# eib-64-nanoz-adapter.net
KiCad netlist of a schematic drawn in EAGLE
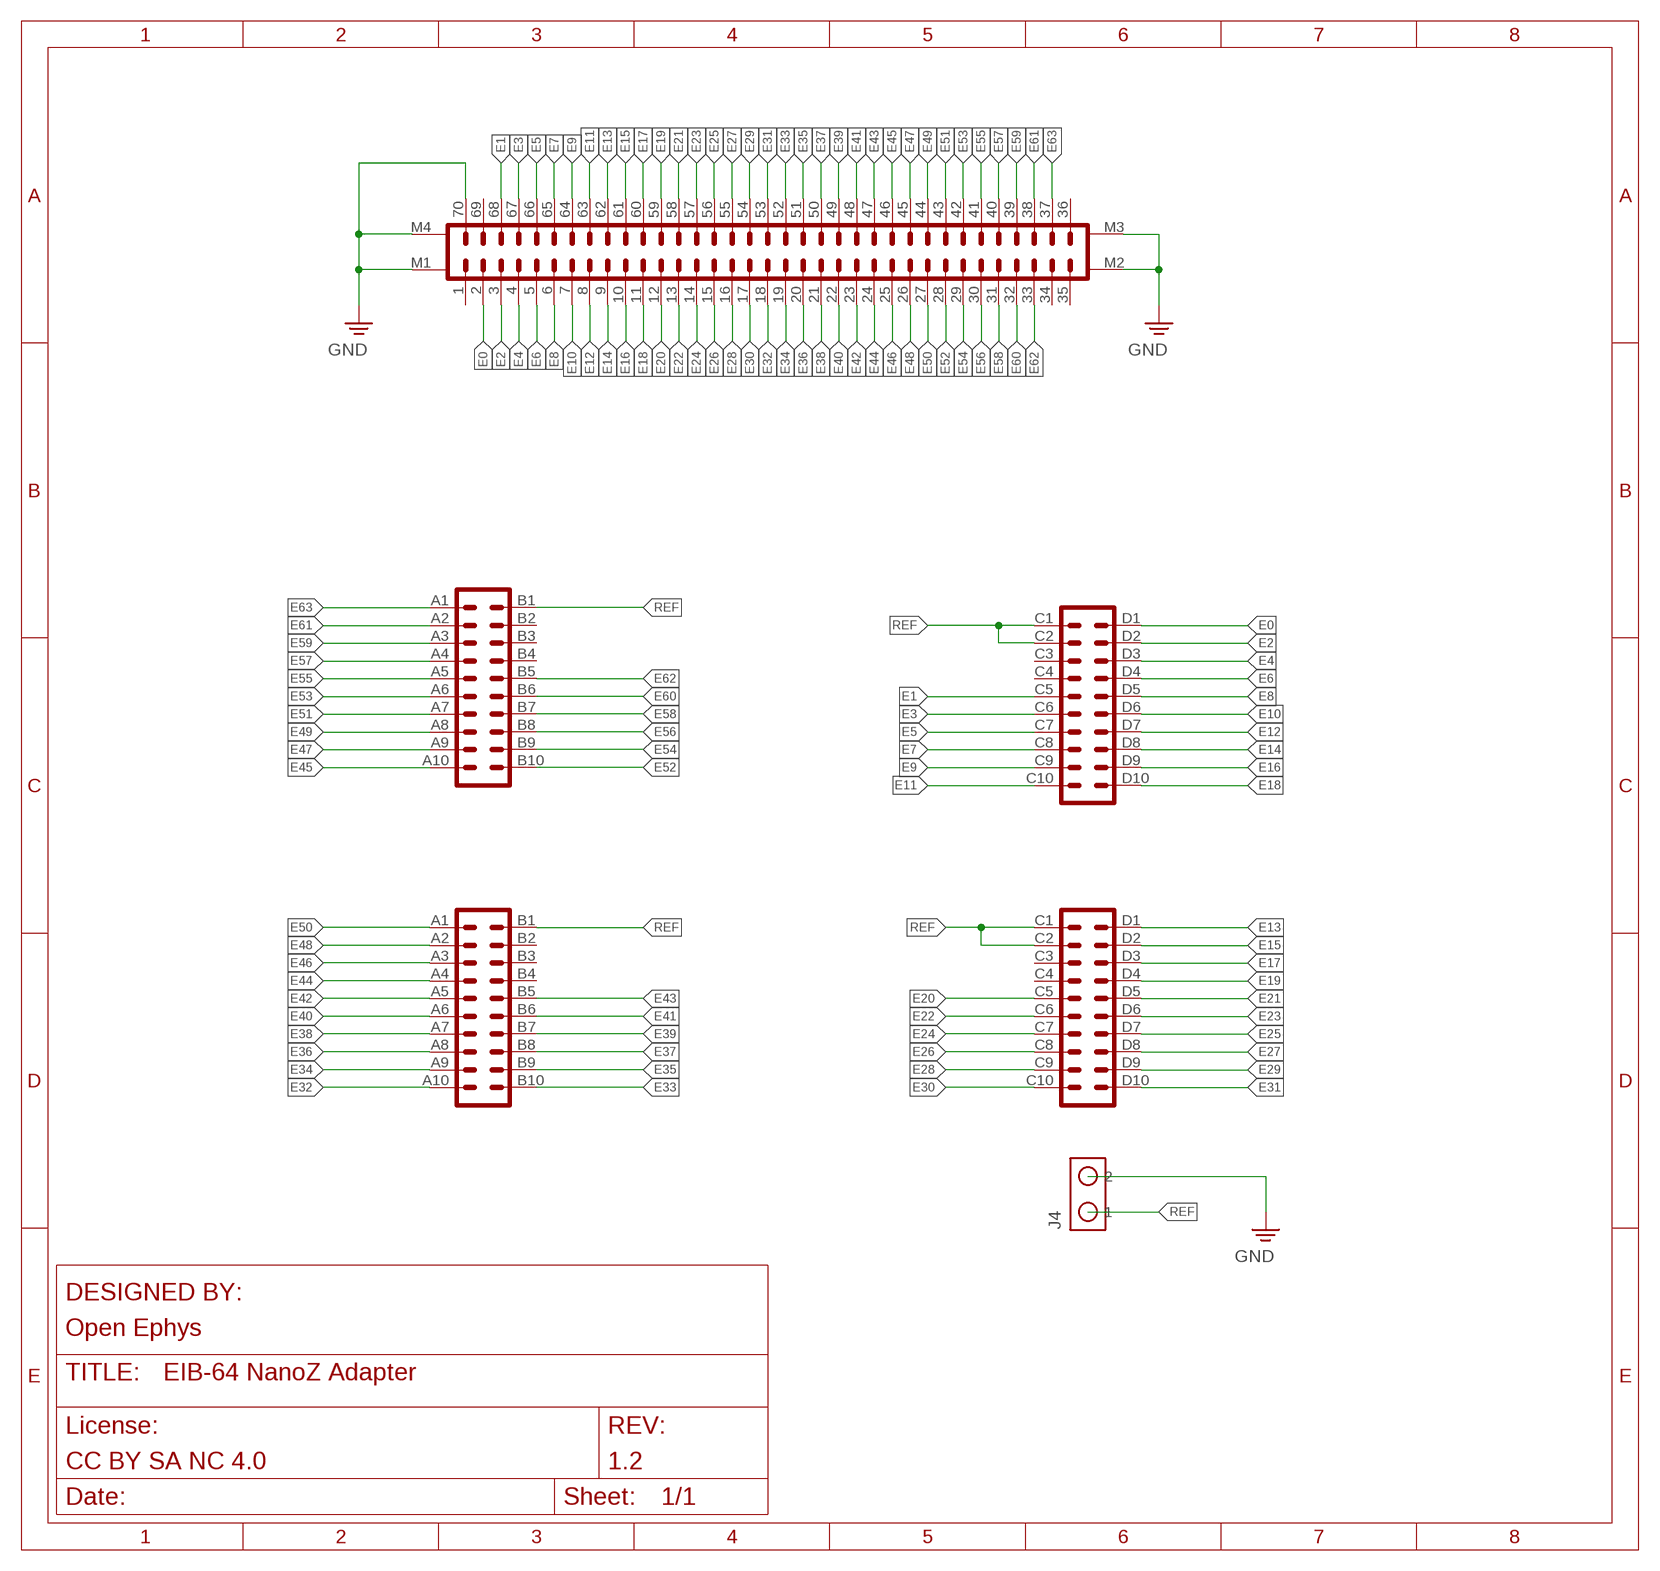
[diagram p0: schematic, sheet 1]

(export (version "E")
  (design (tool "Eeschema 10.0.6"))
  (components
    (comp (ref "J1")
      (value "DF40-REC")
      (footprint "eagle-import:DF40-70HEAD")
      (libsource (lib "eagle-import") (part "PINHD-2X35+4_DF40-70HEAD"))
    )
    (comp (ref "J2")
      (value "PINHD-4X10_MOLC-THRU")
      (footprint "eagle-import:MOLC-110-11-S-Q")
      (libsource (lib "eagle-import") (part "PINHD-4X10_MOLC-THRU"))
    )
    (comp (ref "J3")
      (value "PINHD-4X10_MOLC-THRU")
      (footprint "eagle-import:MOLC-110-11-S-Q")
      (libsource (lib "eagle-import") (part "PINHD-4X10_MOLC-THRU"))
    )
    (comp (ref "J4")
      (value "SCREW2")
      (footprint "eagle-import:SCREW2")
      (libsource (lib "eagle-import") (part "SCREW2"))
    )
  )
  (nets
    (net (code "1") (name "E0") (class "Default")
      (node (ref "J1") (pin "2") (pinfunction "2_2") (pintype "bidirectional"))
      (node (ref "J2") (pin "D1") (pinfunction "20_D1") (pintype "bidirectional"))
    )
    (net (code "2") (name "E1") (class "Default")
      (node (ref "J1") (pin "68") (pinfunction "68_68") (pintype "bidirectional"))
      (node (ref "J2") (pin "C5") (pinfunction "5_C5") (pintype "bidirectional"))
    )
    (net (code "3") (name "E2") (class "Default")
      (node (ref "J1") (pin "3") (pinfunction "3_3") (pintype "bidirectional"))
      (node (ref "J2") (pin "D2") (pinfunction "19_D2") (pintype "bidirectional"))
    )
    (net (code "4") (name "E3") (class "Default")
      (node (ref "J1") (pin "67") (pinfunction "67_67") (pintype "bidirectional"))
      (node (ref "J2") (pin "C6") (pinfunction "6_C6") (pintype "bidirectional"))
    )
    (net (code "5") (name "E4") (class "Default")
      (node (ref "J1") (pin "4") (pinfunction "4_4") (pintype "bidirectional"))
      (node (ref "J2") (pin "D3") (pinfunction "18_D3") (pintype "bidirectional"))
    )
    (net (code "6") (name "E5") (class "Default")
      (node (ref "J1") (pin "66") (pinfunction "66_66") (pintype "bidirectional"))
      (node (ref "J2") (pin "C7") (pinfunction "7_C7") (pintype "bidirectional"))
    )
    (net (code "7") (name "E6") (class "Default")
      (node (ref "J1") (pin "5") (pinfunction "5_5") (pintype "bidirectional"))
      (node (ref "J2") (pin "D4") (pinfunction "17_D4") (pintype "bidirectional"))
    )
    (net (code "8") (name "E7") (class "Default")
      (node (ref "J1") (pin "65") (pinfunction "65_65") (pintype "bidirectional"))
      (node (ref "J2") (pin "C8") (pinfunction "8_C8") (pintype "bidirectional"))
    )
    (net (code "9") (name "E8") (class "Default")
      (node (ref "J1") (pin "6") (pinfunction "6_6") (pintype "bidirectional"))
      (node (ref "J2") (pin "D5") (pinfunction "16_D5") (pintype "bidirectional"))
    )
    (net (code "10") (name "E9") (class "Default")
      (node (ref "J1") (pin "64") (pinfunction "64_64") (pintype "bidirectional"))
      (node (ref "J2") (pin "C9") (pinfunction "9_C9") (pintype "bidirectional"))
    )
    (net (code "11") (name "E10") (class "Default")
      (node (ref "J1") (pin "7") (pinfunction "7_7") (pintype "bidirectional"))
      (node (ref "J2") (pin "D6") (pinfunction "15_D6") (pintype "bidirectional"))
    )
    (net (code "12") (name "E11") (class "Default")
      (node (ref "J1") (pin "63") (pinfunction "63_63") (pintype "bidirectional"))
      (node (ref "J2") (pin "C10") (pinfunction "10_C10") (pintype "bidirectional"))
    )
    (net (code "13") (name "E12") (class "Default")
      (node (ref "J1") (pin "8") (pinfunction "8_8") (pintype "bidirectional"))
      (node (ref "J2") (pin "D7") (pinfunction "14_D7") (pintype "bidirectional"))
    )
    (net (code "14") (name "E13") (class "Default")
      (node (ref "J1") (pin "62") (pinfunction "62_62") (pintype "bidirectional"))
      (node (ref "J3") (pin "D1") (pinfunction "20_D1") (pintype "bidirectional"))
    )
    (net (code "15") (name "E14") (class "Default")
      (node (ref "J1") (pin "9") (pinfunction "9_9") (pintype "bidirectional"))
      (node (ref "J2") (pin "D8") (pinfunction "13_D8") (pintype "bidirectional"))
    )
    (net (code "16") (name "E15") (class "Default")
      (node (ref "J1") (pin "61") (pinfunction "61_61") (pintype "bidirectional"))
      (node (ref "J3") (pin "D2") (pinfunction "19_D2") (pintype "bidirectional"))
    )
    (net (code "17") (name "E16") (class "Default")
      (node (ref "J1") (pin "10") (pinfunction "10_10") (pintype "bidirectional"))
      (node (ref "J2") (pin "D9") (pinfunction "12_D9") (pintype "bidirectional"))
    )
    (net (code "18") (name "E17") (class "Default")
      (node (ref "J1") (pin "60") (pinfunction "60_60") (pintype "bidirectional"))
      (node (ref "J3") (pin "D3") (pinfunction "18_D3") (pintype "bidirectional"))
    )
    (net (code "19") (name "E18") (class "Default")
      (node (ref "J1") (pin "11") (pinfunction "11_11") (pintype "bidirectional"))
      (node (ref "J2") (pin "D10") (pinfunction "11_D10") (pintype "bidirectional"))
    )
    (net (code "20") (name "E19") (class "Default")
      (node (ref "J1") (pin "59") (pinfunction "59_59") (pintype "bidirectional"))
      (node (ref "J3") (pin "D4") (pinfunction "17_D4") (pintype "bidirectional"))
    )
    (net (code "21") (name "E20") (class "Default")
      (node (ref "J1") (pin "12") (pinfunction "12_12") (pintype "bidirectional"))
      (node (ref "J3") (pin "C5") (pinfunction "5_C5") (pintype "bidirectional"))
    )
    (net (code "22") (name "E21") (class "Default")
      (node (ref "J1") (pin "58") (pinfunction "58_58") (pintype "bidirectional"))
      (node (ref "J3") (pin "D5") (pinfunction "16_D5") (pintype "bidirectional"))
    )
    (net (code "23") (name "E22") (class "Default")
      (node (ref "J1") (pin "13") (pinfunction "13_13") (pintype "bidirectional"))
      (node (ref "J3") (pin "C6") (pinfunction "6_C6") (pintype "bidirectional"))
    )
    (net (code "24") (name "E23") (class "Default")
      (node (ref "J1") (pin "57") (pinfunction "57_57") (pintype "bidirectional"))
      (node (ref "J3") (pin "D6") (pinfunction "15_D6") (pintype "bidirectional"))
    )
    (net (code "25") (name "E24") (class "Default")
      (node (ref "J1") (pin "14") (pinfunction "14_14") (pintype "bidirectional"))
      (node (ref "J3") (pin "C7") (pinfunction "7_C7") (pintype "bidirectional"))
    )
    (net (code "26") (name "E25") (class "Default")
      (node (ref "J1") (pin "56") (pinfunction "56_56") (pintype "bidirectional"))
      (node (ref "J3") (pin "D7") (pinfunction "14_D7") (pintype "bidirectional"))
    )
    (net (code "27") (name "E26") (class "Default")
      (node (ref "J1") (pin "15") (pinfunction "15_15") (pintype "bidirectional"))
      (node (ref "J3") (pin "C8") (pinfunction "8_C8") (pintype "bidirectional"))
    )
    (net (code "28") (name "E27") (class "Default")
      (node (ref "J1") (pin "55") (pinfunction "55_55") (pintype "bidirectional"))
      (node (ref "J3") (pin "D8") (pinfunction "13_D8") (pintype "bidirectional"))
    )
    (net (code "29") (name "E28") (class "Default")
      (node (ref "J1") (pin "16") (pinfunction "16_16") (pintype "bidirectional"))
      (node (ref "J3") (pin "C9") (pinfunction "9_C9") (pintype "bidirectional"))
    )
    (net (code "30") (name "E29") (class "Default")
      (node (ref "J1") (pin "54") (pinfunction "54_54") (pintype "bidirectional"))
      (node (ref "J3") (pin "D9") (pinfunction "12_D9") (pintype "bidirectional"))
    )
    (net (code "31") (name "E30") (class "Default")
      (node (ref "J1") (pin "17") (pinfunction "17_17") (pintype "bidirectional"))
      (node (ref "J3") (pin "C10") (pinfunction "10_C10") (pintype "bidirectional"))
    )
    (net (code "32") (name "E31") (class "Default")
      (node (ref "J1") (pin "53") (pinfunction "53_53") (pintype "bidirectional"))
      (node (ref "J3") (pin "D10") (pinfunction "11_D10") (pintype "bidirectional"))
    )
    (net (code "33") (name "E32") (class "Default")
      (node (ref "J1") (pin "18") (pinfunction "18_18") (pintype "bidirectional"))
      (node (ref "J3") (pin "A10") (pinfunction "10_A10") (pintype "bidirectional"))
    )
    (net (code "34") (name "E33") (class "Default")
      (node (ref "J1") (pin "52") (pinfunction "52_52") (pintype "bidirectional"))
      (node (ref "J3") (pin "B10") (pinfunction "11_B10") (pintype "bidirectional"))
    )
    (net (code "35") (name "E34") (class "Default")
      (node (ref "J1") (pin "19") (pinfunction "19_19") (pintype "bidirectional"))
      (node (ref "J3") (pin "A9") (pinfunction "9_A9") (pintype "bidirectional"))
    )
    (net (code "36") (name "E35") (class "Default")
      (node (ref "J1") (pin "51") (pinfunction "51_51") (pintype "bidirectional"))
      (node (ref "J3") (pin "B9") (pinfunction "12_B9") (pintype "bidirectional"))
    )
    (net (code "37") (name "E36") (class "Default")
      (node (ref "J1") (pin "20") (pinfunction "20_20") (pintype "bidirectional"))
      (node (ref "J3") (pin "A8") (pinfunction "8_A8") (pintype "bidirectional"))
    )
    (net (code "38") (name "E37") (class "Default")
      (node (ref "J1") (pin "50") (pinfunction "50_50") (pintype "bidirectional"))
      (node (ref "J3") (pin "B8") (pinfunction "13_B8") (pintype "bidirectional"))
    )
    (net (code "39") (name "E38") (class "Default")
      (node (ref "J1") (pin "21") (pinfunction "21_21") (pintype "bidirectional"))
      (node (ref "J3") (pin "A7") (pinfunction "7_A7") (pintype "bidirectional"))
    )
    (net (code "40") (name "E39") (class "Default")
      (node (ref "J1") (pin "49") (pinfunction "49_49") (pintype "bidirectional"))
      (node (ref "J3") (pin "B7") (pinfunction "14_B7") (pintype "bidirectional"))
    )
    (net (code "41") (name "E40") (class "Default")
      (node (ref "J1") (pin "22") (pinfunction "22_22") (pintype "bidirectional"))
      (node (ref "J3") (pin "A6") (pinfunction "6_A6") (pintype "bidirectional"))
    )
    (net (code "42") (name "E41") (class "Default")
      (node (ref "J1") (pin "48") (pinfunction "48_48") (pintype "bidirectional"))
      (node (ref "J3") (pin "B6") (pinfunction "15_B6") (pintype "bidirectional"))
    )
    (net (code "43") (name "E42") (class "Default")
      (node (ref "J1") (pin "23") (pinfunction "23_23") (pintype "bidirectional"))
      (node (ref "J3") (pin "A5") (pinfunction "5_A5") (pintype "bidirectional"))
    )
    (net (code "44") (name "E43") (class "Default")
      (node (ref "J1") (pin "47") (pinfunction "47_47") (pintype "bidirectional"))
      (node (ref "J3") (pin "B5") (pinfunction "16_B5") (pintype "bidirectional"))
    )
    (net (code "45") (name "E44") (class "Default")
      (node (ref "J1") (pin "24") (pinfunction "24_24") (pintype "bidirectional"))
      (node (ref "J3") (pin "A4") (pinfunction "4_A4") (pintype "bidirectional"))
    )
    (net (code "46") (name "E45") (class "Default")
      (node (ref "J1") (pin "46") (pinfunction "46_46") (pintype "bidirectional"))
      (node (ref "J2") (pin "A10") (pinfunction "10_A10") (pintype "bidirectional"))
    )
    (net (code "47") (name "E46") (class "Default")
      (node (ref "J1") (pin "25") (pinfunction "25_25") (pintype "bidirectional"))
      (node (ref "J3") (pin "A3") (pinfunction "3_A3") (pintype "bidirectional"))
    )
    (net (code "48") (name "E47") (class "Default")
      (node (ref "J1") (pin "45") (pinfunction "45_45") (pintype "bidirectional"))
      (node (ref "J2") (pin "A9") (pinfunction "9_A9") (pintype "bidirectional"))
    )
    (net (code "49") (name "E48") (class "Default")
      (node (ref "J1") (pin "26") (pinfunction "26_26") (pintype "bidirectional"))
      (node (ref "J3") (pin "A2") (pinfunction "2_A2") (pintype "bidirectional"))
    )
    (net (code "50") (name "E49") (class "Default")
      (node (ref "J1") (pin "44") (pinfunction "44_44") (pintype "bidirectional"))
      (node (ref "J2") (pin "A8") (pinfunction "8_A8") (pintype "bidirectional"))
    )
    (net (code "51") (name "E50") (class "Default")
      (node (ref "J1") (pin "27") (pinfunction "27_27") (pintype "bidirectional"))
      (node (ref "J3") (pin "A1") (pinfunction "1_A1") (pintype "bidirectional"))
    )
    (net (code "52") (name "E51") (class "Default")
      (node (ref "J1") (pin "43") (pinfunction "43_43") (pintype "bidirectional"))
      (node (ref "J2") (pin "A7") (pinfunction "7_A7") (pintype "bidirectional"))
    )
    (net (code "53") (name "E52") (class "Default")
      (node (ref "J1") (pin "28") (pinfunction "28_28") (pintype "bidirectional"))
      (node (ref "J2") (pin "B10") (pinfunction "11_B10") (pintype "bidirectional"))
    )
    (net (code "54") (name "E53") (class "Default")
      (node (ref "J1") (pin "42") (pinfunction "42_42") (pintype "bidirectional"))
      (node (ref "J2") (pin "A6") (pinfunction "6_A6") (pintype "bidirectional"))
    )
    (net (code "55") (name "E54") (class "Default")
      (node (ref "J1") (pin "29") (pinfunction "29_29") (pintype "bidirectional"))
      (node (ref "J2") (pin "B9") (pinfunction "12_B9") (pintype "bidirectional"))
    )
    (net (code "56") (name "E55") (class "Default")
      (node (ref "J1") (pin "41") (pinfunction "41_41") (pintype "bidirectional"))
      (node (ref "J2") (pin "A5") (pinfunction "5_A5") (pintype "bidirectional"))
    )
    (net (code "57") (name "E56") (class "Default")
      (node (ref "J1") (pin "30") (pinfunction "30_30") (pintype "bidirectional"))
      (node (ref "J2") (pin "B8") (pinfunction "13_B8") (pintype "bidirectional"))
    )
    (net (code "58") (name "E57") (class "Default")
      (node (ref "J1") (pin "40") (pinfunction "40_40") (pintype "bidirectional"))
      (node (ref "J2") (pin "A4") (pinfunction "4_A4") (pintype "bidirectional"))
    )
    (net (code "59") (name "E58") (class "Default")
      (node (ref "J1") (pin "31") (pinfunction "31_31") (pintype "bidirectional"))
      (node (ref "J2") (pin "B7") (pinfunction "14_B7") (pintype "bidirectional"))
    )
    (net (code "60") (name "E59") (class "Default")
      (node (ref "J1") (pin "39") (pinfunction "39_39") (pintype "bidirectional"))
      (node (ref "J2") (pin "A3") (pinfunction "3_A3") (pintype "bidirectional"))
    )
    (net (code "61") (name "E60") (class "Default")
      (node (ref "J1") (pin "32") (pinfunction "32_32") (pintype "bidirectional"))
      (node (ref "J2") (pin "B6") (pinfunction "15_B6") (pintype "bidirectional"))
    )
    (net (code "62") (name "E61") (class "Default")
      (node (ref "J1") (pin "38") (pinfunction "38_38") (pintype "bidirectional"))
      (node (ref "J2") (pin "A2") (pinfunction "2_A2") (pintype "bidirectional"))
    )
    (net (code "63") (name "E62") (class "Default")
      (node (ref "J1") (pin "33") (pinfunction "33_33") (pintype "bidirectional"))
      (node (ref "J2") (pin "B5") (pinfunction "16_B5") (pintype "bidirectional"))
    )
    (net (code "64") (name "E63") (class "Default")
      (node (ref "J1") (pin "37") (pinfunction "37_37") (pintype "bidirectional"))
      (node (ref "J2") (pin "A1") (pinfunction "1_A1") (pintype "bidirectional"))
    )
    (net (code "65") (name "GND") (class "Default")
      (node (ref "J1") (pin "70") (pinfunction "70_70") (pintype "bidirectional"))
      (node (ref "J1") (pin "M1") (pinfunction "M1_M1") (pintype "bidirectional"))
      (node (ref "J1") (pin "M2") (pinfunction "M2_M2") (pintype "bidirectional"))
      (node (ref "J1") (pin "M3") (pinfunction "M3_M3") (pintype "bidirectional"))
      (node (ref "J1") (pin "M4") (pinfunction "M4_M4") (pintype "bidirectional"))
      (node (ref "J4") (pin "P$2") (pinfunction "2_P$2") (pintype "passive"))
    )
    (net (code "66") (name "REF") (class "Default")
      (node (ref "J2") (pin "B1") (pinfunction "20_B1") (pintype "bidirectional"))
      (node (ref "J2") (pin "C1") (pinfunction "1_C1") (pintype "bidirectional"))
      (node (ref "J2") (pin "C2") (pinfunction "2_C2") (pintype "bidirectional"))
      (node (ref "J3") (pin "B1") (pinfunction "20_B1") (pintype "bidirectional"))
      (node (ref "J3") (pin "C1") (pinfunction "1_C1") (pintype "bidirectional"))
      (node (ref "J3") (pin "C2") (pinfunction "2_C2") (pintype "bidirectional"))
      (node (ref "J4") (pin "P$1") (pinfunction "1_P$1") (pintype "passive"))
    )
    (net (code "67") (name "unconnected-(J1-Pad1)") (class "Default")
      (node (ref "J1") (pin "1") (pinfunction "1_1") (pintype "bidirectional"))
    )
    (net (code "68") (name "unconnected-(J1-Pad34)") (class "Default")
      (node (ref "J1") (pin "34") (pinfunction "34_34") (pintype "bidirectional"))
    )
    (net (code "69") (name "unconnected-(J1-Pad35)") (class "Default")
      (node (ref "J1") (pin "35") (pinfunction "35_35") (pintype "bidirectional"))
    )
    (net (code "70") (name "unconnected-(J1-Pad36)") (class "Default")
      (node (ref "J1") (pin "36") (pinfunction "36_36") (pintype "bidirectional"))
    )
    (net (code "71") (name "unconnected-(J1-Pad69)") (class "Default")
      (node (ref "J1") (pin "69") (pinfunction "69_69") (pintype "bidirectional"))
    )
    (net (code "72") (name "unconnected-(J2A-17-PadB4)") (class "Default")
      (node (ref "J2") (pin "B4") (pinfunction "17_B4") (pintype "bidirectional"))
    )
    (net (code "73") (name "unconnected-(J2A-18-PadB3)") (class "Default")
      (node (ref "J2") (pin "B3") (pinfunction "18_B3") (pintype "bidirectional"))
    )
    (net (code "74") (name "unconnected-(J2A-19-PadB2)") (class "Default")
      (node (ref "J2") (pin "B2") (pinfunction "19_B2") (pintype "bidirectional"))
    )
    (net (code "75") (name "unconnected-(J2B-3-PadC3)") (class "Default")
      (node (ref "J2") (pin "C3") (pinfunction "3_C3") (pintype "bidirectional"))
    )
    (net (code "76") (name "unconnected-(J2B-4-PadC4)") (class "Default")
      (node (ref "J2") (pin "C4") (pinfunction "4_C4") (pintype "bidirectional"))
    )
    (net (code "77") (name "unconnected-(J3A-17-PadB4)") (class "Default")
      (node (ref "J3") (pin "B4") (pinfunction "17_B4") (pintype "bidirectional"))
    )
    (net (code "78") (name "unconnected-(J3A-18-PadB3)") (class "Default")
      (node (ref "J3") (pin "B3") (pinfunction "18_B3") (pintype "bidirectional"))
    )
    (net (code "79") (name "unconnected-(J3A-19-PadB2)") (class "Default")
      (node (ref "J3") (pin "B2") (pinfunction "19_B2") (pintype "bidirectional"))
    )
    (net (code "80") (name "unconnected-(J3B-3-PadC3)") (class "Default")
      (node (ref "J3") (pin "C3") (pinfunction "3_C3") (pintype "bidirectional"))
    )
    (net (code "81") (name "unconnected-(J3B-4-PadC4)") (class "Default")
      (node (ref "J3") (pin "C4") (pinfunction "4_C4") (pintype "bidirectional"))
    )
  )
)
